# Power_Card.net
KiCad netlist of a schematic drawn in Altium Designer
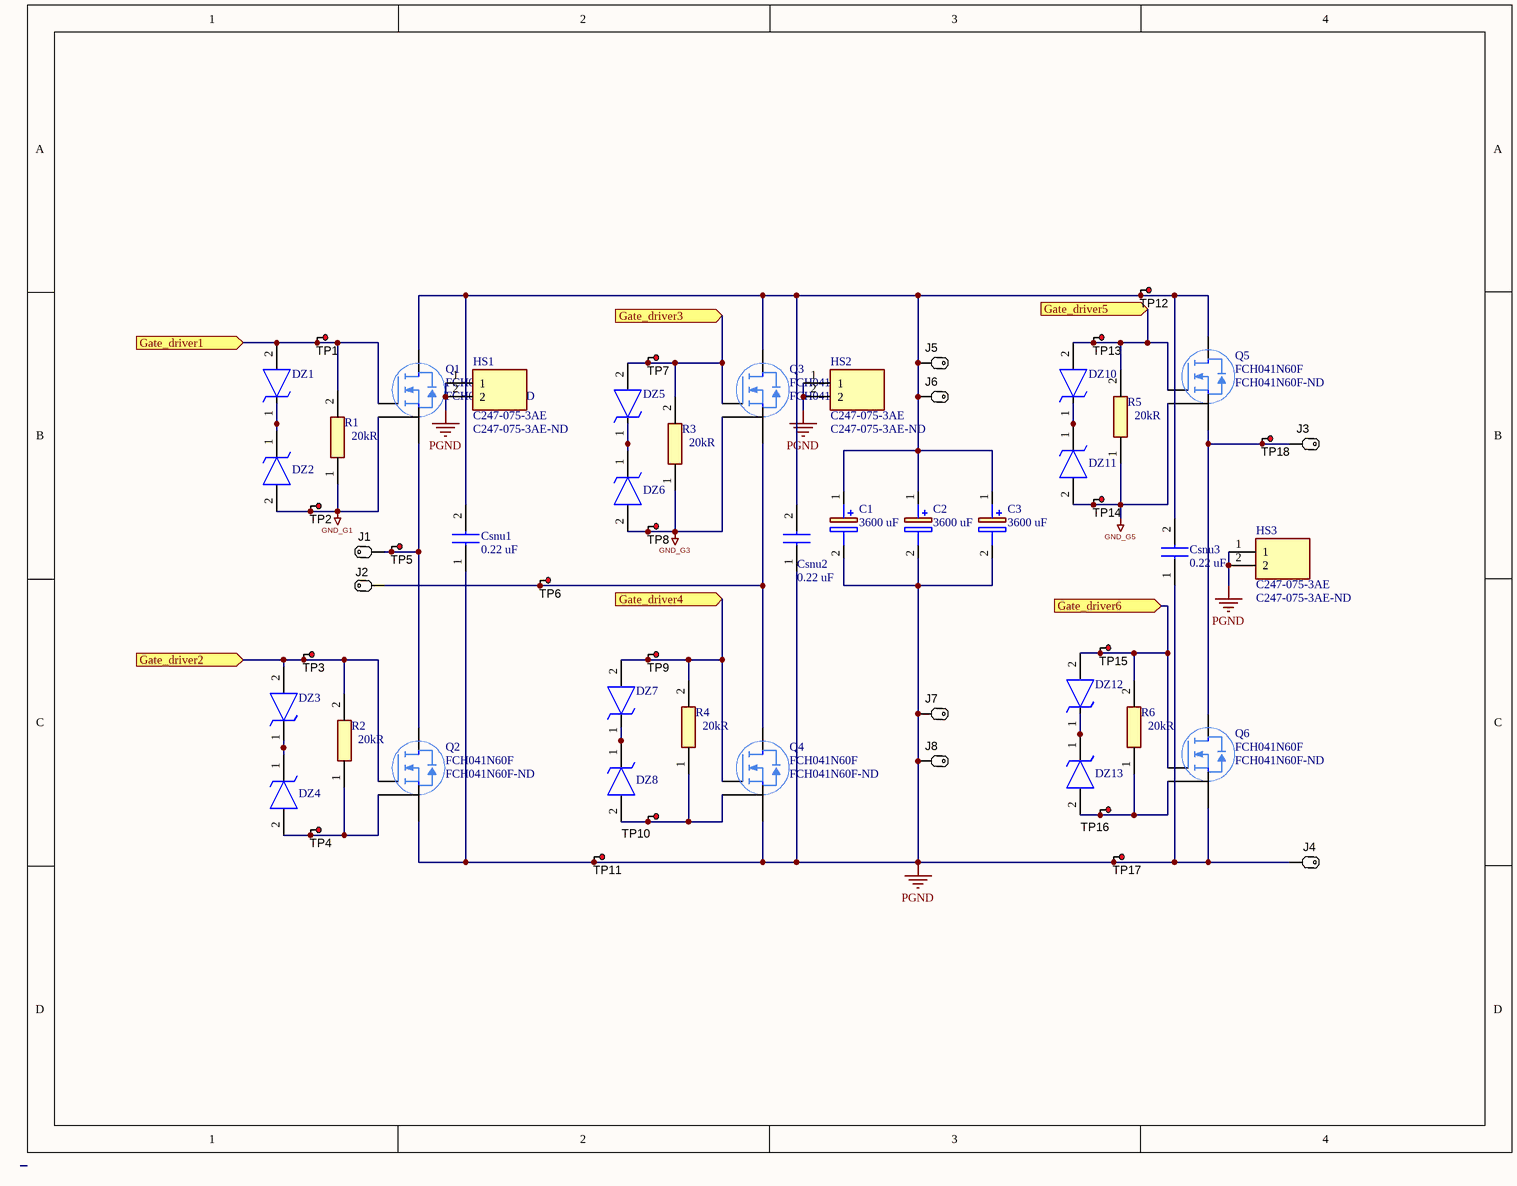
[diagram p0: Power_Card.SchDoc]

(export (version "E")
  (design (tool "Eeschema 10.0.6"))
  (components
    (comp (ref "C1")
      (value "3600 uF")
      (footprint "SamacSys:CAPPRD2220W900D5400H8200")
      (description "Capacitor Polarised")
      (fields (field (name "MANUFACTURER_PART_NUMBER") "ALS70A362KE250"))
      (libsource (lib "sch jasiel") (part "ALS70A362KE250"))
    )
    (comp (ref "C2")
      (value "3600 uF")
      (footprint "SamacSys:CAPPRD2220W900D5400H8200")
      (description "Capacitor Polarised")
      (fields (field (name "MANUFACTURER_PART_NUMBER") "ALS70A362KE250"))
      (libsource (lib "sch jasiel") (part "ALS70A362KE250"))
    )
    (comp (ref "C3")
      (value "3600 uF")
      (footprint "SamacSys:CAPPRD2220W900D5400H8200")
      (description "Capacitor Polarised")
      (fields (field (name "MANUFACTURER_PART_NUMBER") "ALS70A362KE250"))
      (libsource (lib "sch jasiel") (part "ALS70A362KE250"))
    )
    (comp (ref "Csnu1")
      (value "0.22 uF")
      (footprint "SamacSys:224PPB250K")
      (description "CAP FILM 0.22UF 10% 250VDC RAD")
      (fields
        (field (name "MANUFACTURER_PART_NUMBER") "224PPB250K")
        (field (name "MOUSER PART NUMBER") "598-224PPB250K")
      )
      (libsource (lib "sch jasiel") (part "224PPB250K"))
    )
    (comp (ref "Csnu2")
      (value "0.22 uF")
      (footprint "SamacSys:224PPB250K")
      (description "CAP FILM 0.22UF 10% 250VDC RAD")
      (fields
        (field (name "MANUFACTURER_PART_NUMBER") "224PPB250K")
        (field (name "MOUSER PART NUMBER") "598-224PPB250K")
      )
      (libsource (lib "sch jasiel") (part "224PPB250K"))
    )
    (comp (ref "Csnu3")
      (value "0.22 uF")
      (footprint "SamacSys:224PPB250K")
      (description "CAP FILM 0.22UF 10% 250VDC RAD")
      (fields
        (field (name "MANUFACTURER_PART_NUMBER") "224PPB250K")
        (field (name "MOUSER PART NUMBER") "598-224PPB250K")
      )
      (libsource (lib "sch jasiel") (part "224PPB250K"))
    )
    (comp (ref "DZ1")
      (value "SMA6J5.0A")
      (footprint "jasiel:DIOM5026X229N")
      (description "NEXPERIA - BZV55-C15,115 - ZENER-DIODE, 15V, 0.5W, SOD-80C-2")
      (fields
        (field (name "MANUFACTURER") "Nexperia")
        (field (name "MANUFACTURER PART NUMBER") "BZV55-C15,115")
      )
      (libsource (lib "sch jasiel") (part "SMA6J5.0A"))
    )
    (comp (ref "DZ2")
      (value "SMA6J5.0A")
      (footprint "jasiel:DIOM5026X229N")
      (description "NEXPERIA - BZV55-C15,115 - ZENER-DIODE, 15V, 0.5W, SOD-80C-2")
      (fields
        (field (name "MANUFACTURER") "Nexperia")
        (field (name "MANUFACTURER PART NUMBER") "BZV55-C15,115")
      )
      (libsource (lib "sch jasiel") (part "SMA6J5.0A"))
    )
    (comp (ref "DZ3")
      (value "SMA6J5.0A")
      (footprint "jasiel:DIOM5026X229N")
      (description "NEXPERIA - BZV55-C15,115 - ZENER-DIODE, 15V, 0.5W, SOD-80C-2")
      (fields
        (field (name "MANUFACTURER") "Nexperia")
        (field (name "MANUFACTURER PART NUMBER") "BZV55-C15,115")
      )
      (libsource (lib "sch jasiel") (part "SMA6J5.0A"))
    )
    (comp (ref "DZ4")
      (value "SMA6J5.0A")
      (footprint "jasiel:DIOM5026X229N")
      (description "NEXPERIA - BZV55-C15,115 - ZENER-DIODE, 15V, 0.5W, SOD-80C-2")
      (fields
        (field (name "MANUFACTURER") "Nexperia")
        (field (name "MANUFACTURER PART NUMBER") "BZV55-C15,115")
      )
      (libsource (lib "sch jasiel") (part "SMA6J5.0A"))
    )
    (comp (ref "DZ5")
      (value "SMA6J5.0A")
      (footprint "jasiel:DIOM5026X229N")
      (description "NEXPERIA - BZV55-C15,115 - ZENER-DIODE, 15V, 0.5W, SOD-80C-2")
      (fields
        (field (name "MANUFACTURER") "Nexperia")
        (field (name "MANUFACTURER PART NUMBER") "BZV55-C15,115")
      )
      (libsource (lib "sch jasiel") (part "SMA6J5.0A"))
    )
    (comp (ref "DZ6")
      (value "SMA6J5.0A")
      (footprint "jasiel:DIOM5026X229N")
      (description "NEXPERIA - BZV55-C15,115 - ZENER-DIODE, 15V, 0.5W, SOD-80C-2")
      (fields
        (field (name "MANUFACTURER") "Nexperia")
        (field (name "MANUFACTURER PART NUMBER") "BZV55-C15,115")
      )
      (libsource (lib "sch jasiel") (part "SMA6J5.0A"))
    )
    (comp (ref "DZ7")
      (value "SMA6J5.0A")
      (footprint "jasiel:DIOM5026X229N")
      (description "NEXPERIA - BZV55-C15,115 - ZENER-DIODE, 15V, 0.5W, SOD-80C-2")
      (fields
        (field (name "MANUFACTURER") "Nexperia")
        (field (name "MANUFACTURER PART NUMBER") "BZV55-C15,115")
      )
      (libsource (lib "sch jasiel") (part "SMA6J5.0A"))
    )
    (comp (ref "DZ8")
      (value "SMA6J5.0A")
      (footprint "jasiel:DIOM5026X229N")
      (description "NEXPERIA - BZV55-C15,115 - ZENER-DIODE, 15V, 0.5W, SOD-80C-2")
      (fields
        (field (name "MANUFACTURER") "Nexperia")
        (field (name "MANUFACTURER PART NUMBER") "BZV55-C15,115")
      )
      (libsource (lib "sch jasiel") (part "SMA6J5.0A"))
    )
    (comp (ref "DZ10")
      (value "SMA6J5.0A")
      (footprint "jasiel:DIOM5026X229N")
      (description "NEXPERIA - BZV55-C15,115 - ZENER-DIODE, 15V, 0.5W, SOD-80C-2")
      (fields
        (field (name "MANUFACTURER") "Nexperia")
        (field (name "MANUFACTURER PART NUMBER") "BZV55-C15,115")
      )
      (libsource (lib "sch jasiel") (part "SMA6J5.0A"))
    )
    (comp (ref "DZ11")
      (value "SMA6J5.0A")
      (footprint "jasiel:DIOM5026X229N")
      (description "NEXPERIA - BZV55-C15,115 - ZENER-DIODE, 15V, 0.5W, SOD-80C-2")
      (fields
        (field (name "MANUFACTURER") "Nexperia")
        (field (name "MANUFACTURER PART NUMBER") "BZV55-C15,115")
      )
      (libsource (lib "sch jasiel") (part "SMA6J5.0A"))
    )
    (comp (ref "DZ12")
      (value "SMA6J5.0A")
      (footprint "jasiel:DIOM5026X229N")
      (description "NEXPERIA - BZV55-C15,115 - ZENER-DIODE, 15V, 0.5W, SOD-80C-2")
      (fields
        (field (name "MANUFACTURER") "Nexperia")
        (field (name "MANUFACTURER PART NUMBER") "BZV55-C15,115")
      )
      (libsource (lib "sch jasiel") (part "SMA6J5.0A"))
    )
    (comp (ref "DZ13")
      (value "SMA6J5.0A")
      (footprint "jasiel:DIOM5026X229N")
      (description "NEXPERIA - BZV55-C15,115 - ZENER-DIODE, 15V, 0.5W, SOD-80C-2")
      (fields
        (field (name "MANUFACTURER") "Nexperia")
        (field (name "MANUFACTURER PART NUMBER") "BZV55-C15,115")
      )
      (libsource (lib "sch jasiel") (part "SMA6J5.0A"))
    )
    (comp (ref "HS1")
      (value "C247-075-3AE")
      (footprint "jasiel:C2470753AE")
      (description "Heatsink,  TO-247,  75 x 20.47 x 38mm,  Spring Clip Mount")
      (fields
        (field (name "MANUFACTURER") "Ohmite")
        (field (name "SUPPLIER PART NUMBER 1") "C247-075-3AE-ND")
      )
      (libsource (lib "sch jasiel") (part "C247-075-3AE"))
    )
    (comp (ref "HS2")
      (value "C247-075-3AE")
      (footprint "jasiel:C2470753AE")
      (description "Heatsink,  TO-247,  75 x 20.47 x 38mm,  Spring Clip Mount")
      (fields
        (field (name "MANUFACTURER") "Ohmite")
        (field (name "SUPPLIER PART NUMBER 1") "C247-075-3AE-ND")
      )
      (libsource (lib "sch jasiel") (part "C247-075-3AE"))
    )
    (comp (ref "HS3")
      (value "C247-075-3AE")
      (footprint "jasiel:C2470753AE")
      (description "Heatsink,  TO-247,  75 x 20.47 x 38mm,  Spring Clip Mount")
      (fields
        (field (name "MANUFACTURER") "Ohmite")
        (field (name "SUPPLIER PART NUMBER 1") "C247-075-3AE-ND")
      )
      (libsource (lib "sch jasiel") (part "C247-075-3AE"))
    )
    (comp (ref "J1")
      (value "~")
      (footprint "TE_62409-1")
      (description "Quick Disconnect Terminal M 15.8mm 7.5mm Tin Over Copper Automotive Bag")
      (fields
        (field (name "MANUFACTURER") "AMP - TE CONNECTIVITY")
        (field (name "MANUFACTURER PART NUMBER") "62409-1")
      )
      (libsource (lib "sch jasiel") (part "62409-1"))
    )
    (comp (ref "J2")
      (value "~")
      (footprint "TE_62409-1")
      (description "Quick Disconnect Terminal M 15.8mm 7.5mm Tin Over Copper Automotive Bag")
      (fields
        (field (name "MANUFACTURER") "AMP - TE CONNECTIVITY")
        (field (name "MANUFACTURER PART NUMBER") "62409-1")
      )
      (libsource (lib "sch jasiel") (part "62409-1"))
    )
    (comp (ref "J3")
      (value "~")
      (footprint "TE_62409-1")
      (description "Quick Disconnect Terminal M 15.8mm 7.5mm Tin Over Copper Automotive Bag")
      (fields
        (field (name "MANUFACTURER") "AMP - TE CONNECTIVITY")
        (field (name "MANUFACTURER PART NUMBER") "62409-1")
      )
      (libsource (lib "sch jasiel") (part "62409-1"))
    )
    (comp (ref "J4")
      (value "~")
      (footprint "TE_62409-1")
      (description "Quick Disconnect Terminal M 15.8mm 7.5mm Tin Over Copper Automotive Bag")
      (fields
        (field (name "MANUFACTURER") "AMP - TE CONNECTIVITY")
        (field (name "MANUFACTURER PART NUMBER") "62409-1")
      )
      (libsource (lib "sch jasiel") (part "62409-1"))
    )
    (comp (ref "J5")
      (value "~")
      (footprint "TE_62409-1")
      (description "Quick Disconnect Terminal M 15.8mm 7.5mm Tin Over Copper Automotive Bag")
      (fields
        (field (name "MANUFACTURER") "AMP - TE CONNECTIVITY")
        (field (name "MANUFACTURER PART NUMBER") "62409-1")
      )
      (libsource (lib "sch jasiel") (part "62409-1"))
    )
    (comp (ref "J6")
      (value "~")
      (footprint "TE_62409-1")
      (description "Quick Disconnect Terminal M 15.8mm 7.5mm Tin Over Copper Automotive Bag")
      (fields
        (field (name "MANUFACTURER") "AMP - TE CONNECTIVITY")
        (field (name "MANUFACTURER PART NUMBER") "62409-1")
      )
      (libsource (lib "sch jasiel") (part "62409-1"))
    )
    (comp (ref "J7")
      (value "~")
      (footprint "TE_62409-1")
      (description "Quick Disconnect Terminal M 15.8mm 7.5mm Tin Over Copper Automotive Bag")
      (fields
        (field (name "MANUFACTURER") "AMP - TE CONNECTIVITY")
        (field (name "MANUFACTURER PART NUMBER") "62409-1")
      )
      (libsource (lib "sch jasiel") (part "62409-1"))
    )
    (comp (ref "J8")
      (value "~")
      (footprint "TE_62409-1")
      (description "Quick Disconnect Terminal M 15.8mm 7.5mm Tin Over Copper Automotive Bag")
      (fields
        (field (name "MANUFACTURER") "AMP - TE CONNECTIVITY")
        (field (name "MANUFACTURER PART NUMBER") "62409-1")
      )
      (libsource (lib "sch jasiel") (part "62409-1"))
    )
    (comp (ref "Q1")
      (value "FCH041N60F")
      (footprint "TO-247-4L_FCH041N60F")
      (description "MOSFET 600V N-Channel MOSFET, FRFET")
      (fields
        (field (name "SUPPLIER PART NUMBER 1") "FCH041N60F-ND")
        (field (name "MANUFACTURER") "ON Semiconductor / Fairchild")
      )
      (libsource (lib "sch jasiel") (part "FCH041N60F"))
    )
    (comp (ref "Q2")
      (value "FCH041N60F")
      (footprint "TO-247-4L_FCH041N60F")
      (description "MOSFET 600V N-Channel MOSFET, FRFET")
      (fields
        (field (name "SUPPLIER PART NUMBER 1") "FCH041N60F-ND")
        (field (name "MANUFACTURER") "ON Semiconductor / Fairchild")
      )
      (libsource (lib "sch jasiel") (part "FCH041N60F"))
    )
    (comp (ref "Q3")
      (value "FCH041N60F")
      (footprint "TO-247-4L_FCH041N60F")
      (description "MOSFET 600V N-Channel MOSFET, FRFET")
      (fields
        (field (name "SUPPLIER PART NUMBER 1") "FCH041N60F-ND")
        (field (name "MANUFACTURER") "ON Semiconductor / Fairchild")
      )
      (libsource (lib "sch jasiel") (part "FCH041N60F"))
    )
    (comp (ref "Q4")
      (value "FCH041N60F")
      (footprint "TO-247-4L_FCH041N60F")
      (description "MOSFET 600V N-Channel MOSFET, FRFET")
      (fields
        (field (name "SUPPLIER PART NUMBER 1") "FCH041N60F-ND")
        (field (name "MANUFACTURER") "ON Semiconductor / Fairchild")
      )
      (libsource (lib "sch jasiel") (part "FCH041N60F"))
    )
    (comp (ref "Q5")
      (value "FCH041N60F")
      (footprint "TO-247-4L_FCH041N60F")
      (description "MOSFET 600V N-Channel MOSFET, FRFET")
      (fields
        (field (name "SUPPLIER PART NUMBER 1") "FCH041N60F-ND")
        (field (name "MANUFACTURER") "ON Semiconductor / Fairchild")
      )
      (libsource (lib "sch jasiel") (part "FCH041N60F"))
    )
    (comp (ref "Q6")
      (value "FCH041N60F")
      (footprint "TO-247-4L_FCH041N60F")
      (description "MOSFET 600V N-Channel MOSFET, FRFET")
      (fields
        (field (name "SUPPLIER PART NUMBER 1") "FCH041N60F-ND")
        (field (name "MANUFACTURER") "ON Semiconductor / Fairchild")
      )
      (libsource (lib "sch jasiel") (part "FCH041N60F"))
    )
    (comp (ref "R1")
      (value "~")
      (footprint "SamacSys:RESC3216X70N")
      (description "RES SMD 20K OHM 5% 1/4W 1206")
      (fields
        (field (name "MANUFACTURER_PART_NUMBER") "RN73H2BTTD1001B10")
        (field (name "MANUFACTURER") "Stackpole Electronics")
        (field (name "RESISTANCE") "20kR")
      )
      (libsource (lib "sch jasiel") (part "RMCF1206JT20K0‎‎"))
    )
    (comp (ref "R2")
      (value "~")
      (footprint "SamacSys:RESC3216X70N")
      (description "RES SMD 20K OHM 5% 1/4W 1206")
      (fields
        (field (name "MANUFACTURER_PART_NUMBER") "RN73H2BTTD1001B10")
        (field (name "MANUFACTURER") "Stackpole Electronics")
        (field (name "RESISTANCE") "20kR")
      )
      (libsource (lib "sch jasiel") (part "RMCF1206JT20K0‎‎"))
    )
    (comp (ref "R3")
      (value "~")
      (footprint "SamacSys:RESC3216X70N")
      (description "RES SMD 20K OHM 5% 1/4W 1206")
      (fields
        (field (name "MANUFACTURER_PART_NUMBER") "RN73H2BTTD1001B10")
        (field (name "MANUFACTURER") "Stackpole Electronics")
        (field (name "RESISTANCE") "20kR")
      )
      (libsource (lib "sch jasiel") (part "RMCF1206JT20K0‎‎"))
    )
    (comp (ref "R4")
      (value "~")
      (footprint "SamacSys:RESC3216X70N")
      (description "RES SMD 20K OHM 5% 1/4W 1206")
      (fields
        (field (name "MANUFACTURER_PART_NUMBER") "RN73H2BTTD1001B10")
        (field (name "MANUFACTURER") "Stackpole Electronics")
        (field (name "RESISTANCE") "20kR")
      )
      (libsource (lib "sch jasiel") (part "RMCF1206JT20K0‎‎"))
    )
    (comp (ref "R5")
      (value "~")
      (footprint "SamacSys:RESC3216X70N")
      (description "RES SMD 20K OHM 5% 1/4W 1206")
      (fields
        (field (name "MANUFACTURER_PART_NUMBER") "RN73H2BTTD1001B10")
        (field (name "MANUFACTURER") "Stackpole Electronics")
        (field (name "RESISTANCE") "20kR")
      )
      (libsource (lib "sch jasiel") (part "RMCF1206JT20K0‎‎"))
    )
    (comp (ref "R6")
      (value "~")
      (footprint "SamacSys:RESC3216X70N")
      (description "RES SMD 20K OHM 5% 1/4W 1206")
      (fields
        (field (name "MANUFACTURER_PART_NUMBER") "RN73H2BTTD1001B10")
        (field (name "MANUFACTURER") "Stackpole Electronics")
        (field (name "RESISTANCE") "20kR")
      )
      (libsource (lib "sch jasiel") (part "RMCF1206JT20K0‎‎"))
    )
    (comp (ref "TP1")
      (value "5010")
      (footprint "Keystone5010")
      (description "Test Point, Multipurpose, Red, TH")
      (fields (field (name "MANUFACTURER") "Keystone") (field (name "PUBLISHER") "Texas Instruments"))
      (libsource (lib "sch jasiel") (part "5010"))
    )
    (comp (ref "TP2")
      (value "5010")
      (footprint "Keystone5010")
      (description "Test Point, Multipurpose, Red, TH")
      (fields (field (name "MANUFACTURER") "Keystone") (field (name "PUBLISHER") "Texas Instruments"))
      (libsource (lib "sch jasiel") (part "5010"))
    )
    (comp (ref "TP3")
      (value "5010")
      (footprint "Keystone5010")
      (description "Test Point, Multipurpose, Red, TH")
      (fields (field (name "MANUFACTURER") "Keystone") (field (name "PUBLISHER") "Texas Instruments"))
      (libsource (lib "sch jasiel") (part "5010"))
    )
    (comp (ref "TP4")
      (value "5010")
      (footprint "Keystone5010")
      (description "Test Point, Multipurpose, Red, TH")
      (fields (field (name "MANUFACTURER") "Keystone") (field (name "PUBLISHER") "Texas Instruments"))
      (libsource (lib "sch jasiel") (part "5010"))
    )
    (comp (ref "TP5")
      (value "5010")
      (footprint "Keystone5010")
      (description "Test Point, Multipurpose, Red, TH")
      (fields (field (name "MANUFACTURER") "Keystone") (field (name "PUBLISHER") "Texas Instruments"))
      (libsource (lib "sch jasiel") (part "5010"))
    )
    (comp (ref "TP6")
      (value "5010")
      (footprint "Keystone5010")
      (description "Test Point, Multipurpose, Red, TH")
      (fields (field (name "MANUFACTURER") "Keystone") (field (name "PUBLISHER") "Texas Instruments"))
      (libsource (lib "sch jasiel") (part "5010"))
    )
    (comp (ref "TP7")
      (value "5010")
      (footprint "Keystone5010")
      (description "Test Point, Multipurpose, Red, TH")
      (fields (field (name "MANUFACTURER") "Keystone") (field (name "PUBLISHER") "Texas Instruments"))
      (libsource (lib "sch jasiel") (part "5010"))
    )
    (comp (ref "TP8")
      (value "5010")
      (footprint "Keystone5010")
      (description "Test Point, Multipurpose, Red, TH")
      (fields (field (name "MANUFACTURER") "Keystone") (field (name "PUBLISHER") "Texas Instruments"))
      (libsource (lib "sch jasiel") (part "5010"))
    )
    (comp (ref "TP9")
      (value "5010")
      (footprint "Keystone5010")
      (description "Test Point, Multipurpose, Red, TH")
      (fields (field (name "MANUFACTURER") "Keystone") (field (name "PUBLISHER") "Texas Instruments"))
      (libsource (lib "sch jasiel") (part "5010"))
    )
    (comp (ref "TP10")
      (value "5010")
      (footprint "Keystone5010")
      (description "Test Point, Multipurpose, Red, TH")
      (fields (field (name "MANUFACTURER") "Keystone") (field (name "PUBLISHER") "Texas Instruments"))
      (libsource (lib "sch jasiel") (part "5010"))
    )
    (comp (ref "TP11")
      (value "5010")
      (footprint "Keystone5010")
      (description "Test Point, Multipurpose, Red, TH")
      (fields (field (name "MANUFACTURER") "Keystone") (field (name "PUBLISHER") "Texas Instruments"))
      (libsource (lib "sch jasiel") (part "5010"))
    )
    (comp (ref "TP12")
      (value "5010")
      (footprint "Keystone5010")
      (description "Test Point, Multipurpose, Red, TH")
      (fields (field (name "MANUFACTURER") "Keystone") (field (name "PUBLISHER") "Texas Instruments"))
      (libsource (lib "sch jasiel") (part "5010"))
    )
    (comp (ref "TP13")
      (value "5010")
      (footprint "Keystone5010")
      (description "Test Point, Multipurpose, Red, TH")
      (fields (field (name "MANUFACTURER") "Keystone") (field (name "PUBLISHER") "Texas Instruments"))
      (libsource (lib "sch jasiel") (part "5010"))
    )
    (comp (ref "TP14")
      (value "5010")
      (footprint "Keystone5010")
      (description "Test Point, Multipurpose, Red, TH")
      (fields (field (name "MANUFACTURER") "Keystone") (field (name "PUBLISHER") "Texas Instruments"))
      (libsource (lib "sch jasiel") (part "5010"))
    )
    (comp (ref "TP15")
      (value "5010")
      (footprint "Keystone5010")
      (description "Test Point, Multipurpose, Red, TH")
      (fields (field (name "MANUFACTURER") "Keystone") (field (name "PUBLISHER") "Texas Instruments"))
      (libsource (lib "sch jasiel") (part "5010"))
    )
    (comp (ref "TP16")
      (value "5010")
      (footprint "Keystone5010")
      (description "Test Point, Multipurpose, Red, TH")
      (fields (field (name "MANUFACTURER") "Keystone") (field (name "PUBLISHER") "Texas Instruments"))
      (libsource (lib "sch jasiel") (part "5010"))
    )
    (comp (ref "TP17")
      (value "5010")
      (footprint "Keystone5010")
      (description "Test Point, Multipurpose, Red, TH")
      (fields (field (name "MANUFACTURER") "Keystone") (field (name "PUBLISHER") "Texas Instruments"))
      (libsource (lib "sch jasiel") (part "5010"))
    )
    (comp (ref "TP18")
      (value "5010")
      (footprint "Keystone5010")
      (description "Test Point, Multipurpose, Red, TH")
      (fields (field (name "MANUFACTURER") "Keystone") (field (name "PUBLISHER") "Texas Instruments"))
      (libsource (lib "sch jasiel") (part "5010"))
    )
  )
  (nets
    (net (code "1") (name "/Gate_driver1") (class "Default")
      (node (ref "DZ1") (pin "2") (pinfunction "A_2") (pintype "passive"))
      (node (ref "Q1") (pin "4") (pinfunction "G_4") (pintype "passive"))
      (node (ref "R1") (pin "2") (pinfunction "2_2") (pintype "passive"))
      (node (ref "TP1") (pin "1") (pinfunction "1_1") (pintype "passive"))
    )
    (net (code "2") (name "/Gate_driver2") (class "Default")
      (node (ref "DZ3") (pin "2") (pinfunction "A_2") (pintype "passive"))
      (node (ref "Q2") (pin "4") (pinfunction "G_4") (pintype "passive"))
      (node (ref "R2") (pin "2") (pinfunction "2_2") (pintype "passive"))
      (node (ref "TP3") (pin "1") (pinfunction "1_1") (pintype "passive"))
    )
    (net (code "3") (name "/Gate_driver3") (class "Default")
      (node (ref "DZ5") (pin "2") (pinfunction "A_2") (pintype "passive"))
      (node (ref "Q3") (pin "4") (pinfunction "G_4") (pintype "passive"))
      (node (ref "R3") (pin "2") (pinfunction "2_2") (pintype "passive"))
      (node (ref "TP7") (pin "1") (pinfunction "1_1") (pintype "passive"))
    )
    (net (code "4") (name "/Gate_driver4") (class "Default")
      (node (ref "DZ7") (pin "2") (pinfunction "A_2") (pintype "passive"))
      (node (ref "Q4") (pin "4") (pinfunction "G_4") (pintype "passive"))
      (node (ref "R4") (pin "2") (pinfunction "2_2") (pintype "passive"))
      (node (ref "TP9") (pin "1") (pinfunction "1_1") (pintype "passive"))
    )
    (net (code "5") (name "/Gate_driver5") (class "Default")
      (node (ref "DZ10") (pin "2") (pinfunction "A_2") (pintype "passive"))
      (node (ref "Q5") (pin "4") (pinfunction "G_4") (pintype "passive"))
      (node (ref "R5") (pin "2") (pinfunction "2_2") (pintype "passive"))
      (node (ref "TP13") (pin "1") (pinfunction "1_1") (pintype "passive"))
    )
    (net (code "6") (name "/Gate_driver6") (class "Default")
      (node (ref "DZ12") (pin "2") (pinfunction "A_2") (pintype "passive"))
      (node (ref "Q6") (pin "4") (pinfunction "G_4") (pintype "passive"))
      (node (ref "R6") (pin "2") (pinfunction "2_2") (pintype "passive"))
      (node (ref "TP15") (pin "1") (pinfunction "1_1") (pintype "passive"))
    )
    (net (code "7") (name "GND_G1") (class "Default")
      (node (ref "DZ2") (pin "2") (pinfunction "A_2") (pintype "passive"))
      (node (ref "Q1") (pin "3") (pinfunction "S_3") (pintype "passive"))
      (node (ref "R1") (pin "1") (pinfunction "1_1") (pintype "passive"))
      (node (ref "TP2") (pin "1") (pinfunction "1_1") (pintype "passive"))
    )
    (net (code "8") (name "GND_G3") (class "Default")
      (node (ref "DZ6") (pin "2") (pinfunction "A_2") (pintype "passive"))
      (node (ref "Q3") (pin "3") (pinfunction "S_3") (pintype "passive"))
      (node (ref "R3") (pin "1") (pinfunction "1_1") (pintype "passive"))
      (node (ref "TP8") (pin "1") (pinfunction "1_1") (pintype "passive"))
    )
    (net (code "9") (name "GND_G5") (class "Default")
      (node (ref "DZ11") (pin "2") (pinfunction "A_2") (pintype "passive"))
      (node (ref "Q5") (pin "3") (pinfunction "S_3") (pintype "passive"))
      (node (ref "R5") (pin "1") (pinfunction "1_1") (pintype "passive"))
      (node (ref "TP14") (pin "1") (pinfunction "1_1") (pintype "passive"))
    )
    (net (code "10") (name "Net-(C1-+)") (class "Default")
      (node (ref "C1") (pin "1") (pinfunction "+_1") (pintype "power_in"))
      (node (ref "C2") (pin "1") (pinfunction "+_1") (pintype "power_in"))
      (node (ref "C3") (pin "1") (pinfunction "+_1") (pintype "power_in"))
      (node (ref "Csnu1") (pin "2") (pinfunction "2_2") (pintype "passive"))
      (node (ref "Csnu2") (pin "2") (pinfunction "2_2") (pintype "passive"))
      (node (ref "Csnu3") (pin "2") (pinfunction "2_2") (pintype "passive"))
      (node (ref "J5") (pin "1") (pinfunction "P1_1") (pintype "passive"))
      (node (ref "J6") (pin "1") (pinfunction "P1_1") (pintype "passive"))
      (node (ref "Q1") (pin "1") (pinfunction "D_1") (pintype "passive"))
      (node (ref "Q3") (pin "1") (pinfunction "D_1") (pintype "passive"))
      (node (ref "Q5") (pin "1") (pinfunction "D_1") (pintype "passive"))
      (node (ref "TP12") (pin "1") (pinfunction "1_1") (pintype "passive"))
    )
    (net (code "11") (name "Net-(DZ1-K)") (class "Default")
      (node (ref "DZ1") (pin "1") (pinfunction "K_1") (pintype "passive"))
      (node (ref "DZ2") (pin "1") (pinfunction "K_1") (pintype "passive"))
    )
    (net (code "12") (name "Net-(DZ3-K)") (class "Default")
      (node (ref "DZ3") (pin "1") (pinfunction "K_1") (pintype "passive"))
      (node (ref "DZ4") (pin "1") (pinfunction "K_1") (pintype "passive"))
    )
    (net (code "13") (name "Net-(DZ4-A)") (class "Default")
      (node (ref "DZ4") (pin "2") (pinfunction "A_2") (pintype "passive"))
      (node (ref "Q2") (pin "3") (pinfunction "S_3") (pintype "passive"))
      (node (ref "R2") (pin "1") (pinfunction "1_1") (pintype "passive"))
      (node (ref "TP4") (pin "1") (pinfunction "1_1") (pintype "passive"))
    )
    (net (code "14") (name "Net-(DZ5-K)") (class "Default")
      (node (ref "DZ5") (pin "1") (pinfunction "K_1") (pintype "passive"))
      (node (ref "DZ6") (pin "1") (pinfunction "K_1") (pintype "passive"))
    )
    (net (code "15") (name "Net-(DZ7-K)") (class "Default")
      (node (ref "DZ7") (pin "1") (pinfunction "K_1") (pintype "passive"))
      (node (ref "DZ8") (pin "1") (pinfunction "K_1") (pintype "passive"))
    )
    (net (code "16") (name "Net-(DZ8-A)") (class "Default")
      (node (ref "DZ8") (pin "2") (pinfunction "A_2") (pintype "passive"))
      (node (ref "Q4") (pin "3") (pinfunction "S_3") (pintype "passive"))
      (node (ref "R4") (pin "1") (pinfunction "1_1") (pintype "passive"))
      (node (ref "TP10") (pin "1") (pinfunction "1_1") (pintype "passive"))
    )
    (net (code "17") (name "Net-(DZ10-K)") (class "Default")
      (node (ref "DZ10") (pin "1") (pinfunction "K_1") (pintype "passive"))
      (node (ref "DZ11") (pin "1") (pinfunction "K_1") (pintype "passive"))
    )
    (net (code "18") (name "Net-(DZ12-K)") (class "Default")
      (node (ref "DZ12") (pin "1") (pinfunction "K_1") (pintype "passive"))
      (node (ref "DZ13") (pin "1") (pinfunction "K_1") (pintype "passive"))
    )
    (net (code "19") (name "Net-(DZ13-A)") (class "Default")
      (node (ref "DZ13") (pin "2") (pinfunction "A_2") (pintype "passive"))
      (node (ref "Q6") (pin "3") (pinfunction "S_3") (pintype "passive"))
      (node (ref "R6") (pin "1") (pinfunction "1_1") (pintype "passive"))
      (node (ref "TP16") (pin "1") (pinfunction "1_1") (pintype "passive"))
    )
    (net (code "20") (name "Net-(J1-P1)") (class "Default")
      (node (ref "J1") (pin "1") (pinfunction "P1_1") (pintype "passive"))
      (node (ref "Q1") (pin "2") (pinfunction "Power_Source_2") (pintype "passive"))
      (node (ref "Q2") (pin "1") (pinfunction "D_1") (pintype "passive"))
      (node (ref "TP5") (pin "1") (pinfunction "1_1") (pintype "passive"))
    )
    (net (code "21") (name "Net-(J2-P1)") (class "Default")
      (node (ref "J2") (pin "1") (pinfunction "P1_1") (pintype "passive"))
      (node (ref "Q3") (pin "2") (pinfunction "Power_Source_2") (pintype "passive"))
      (node (ref "Q4") (pin "1") (pinfunction "D_1") (pintype "passive"))
      (node (ref "TP6") (pin "1") (pinfunction "1_1") (pintype "passive"))
    )
    (net (code "22") (name "Net-(J3-P1)") (class "Default")
      (node (ref "J3") (pin "1") (pinfunction "P1_1") (pintype "passive"))
      (node (ref "Q5") (pin "2") (pinfunction "Power_Source_2") (pintype "passive"))
      (node (ref "Q6") (pin "1") (pinfunction "D_1") (pintype "passive"))
      (node (ref "TP18") (pin "1") (pinfunction "1_1") (pintype "passive"))
    )
    (net (code "23") (name "PGND") (class "Default")
      (node (ref "C1") (pin "2") (pinfunction "-_2") (pintype "power_in"))
      (node (ref "C2") (pin "2") (pinfunction "-_2") (pintype "power_in"))
      (node (ref "C3") (pin "2") (pinfunction "-_2") (pintype "power_in"))
      (node (ref "Csnu1") (pin "1") (pinfunction "1_1") (pintype "passive"))
      (node (ref "Csnu2") (pin "1") (pinfunction "1_1") (pintype "passive"))
      (node (ref "Csnu3") (pin "1") (pinfunction "1_1") (pintype "passive"))
      (node (ref "HS1") (pin "1") (pinfunction "1_1") (pintype "passive"))
      (node (ref "HS1") (pin "2") (pinfunction "2_2") (pintype "passive"))
      (node (ref "HS2") (pin "1") (pinfunction "1_1") (pintype "passive"))
      (node (ref "HS2") (pin "2") (pinfunction "2_2") (pintype "passive"))
      (node (ref "HS3") (pin "1") (pinfunction "1_1") (pintype "passive"))
      (node (ref "HS3") (pin "2") (pinfunction "2_2") (pintype "passive"))
      (node (ref "J4") (pin "1") (pinfunction "P1_1") (pintype "passive"))
      (node (ref "J7") (pin "1") (pinfunction "P1_1") (pintype "passive"))
      (node (ref "J8") (pin "1") (pinfunction "P1_1") (pintype "passive"))
      (node (ref "Q2") (pin "2") (pinfunction "Power_Source_2") (pintype "passive"))
      (node (ref "Q4") (pin "2") (pinfunction "Power_Source_2") (pintype "passive"))
      (node (ref "Q6") (pin "2") (pinfunction "Power_Source_2") (pintype "passive"))
      (node (ref "TP11") (pin "1") (pinfunction "1_1") (pintype "passive"))
      (node (ref "TP17") (pin "1") (pinfunction "1_1") (pintype "passive"))
    )
  )
)
